# tqfp-sandwich-ui.net
KiCad netlist of a schematic drawn in EAGLE
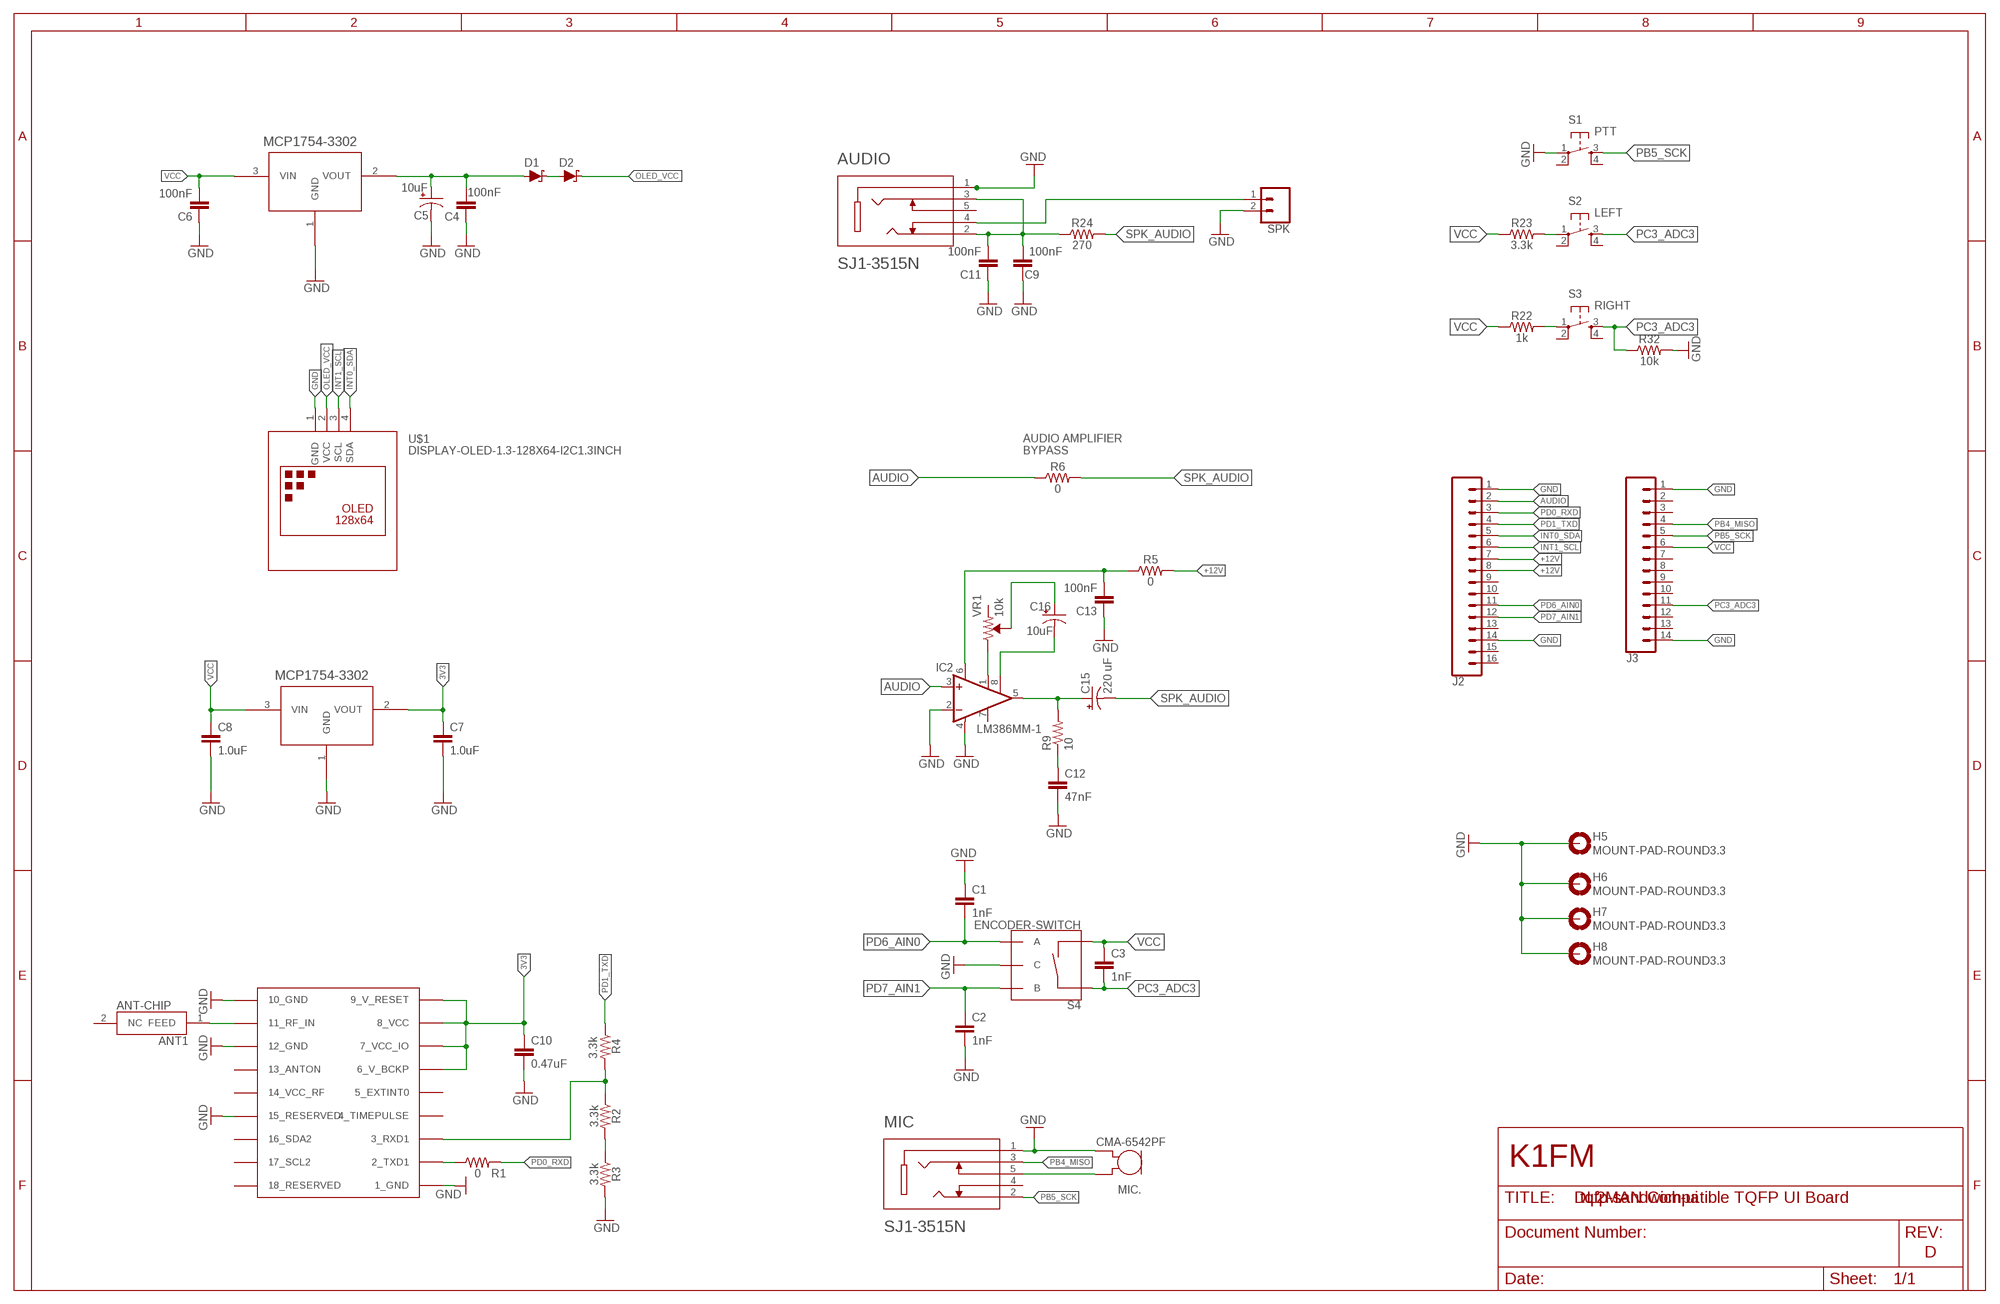
[diagram p0: schematic, sheet 1]

(export (version "E")
  (design (tool "Eeschema 10.0.6"))
  (components
    (comp (ref "ANT-CHIP")
      (value "ANT1")
      (footprint "eagle-import:1575AT43A0040E")
      (fields
        (field (name "MANUFACTURER_PART_NUMBER") "1575AT43A0040E")
        (field (name "MOUSER_PART_NUMBER") "609-1575AT43A0040E")
      )
      (libsource (lib "eagle-import") (part "1575AT43A0040E"))
    )
    (comp (ref "AUDIO")
      (value "SJ1-3515N")
      (footprint "eagle-import:CUI_SJ1-3515N")
      (fields (field (name "MANUFACTURER") "CUI"))
      (libsource (lib "eagle-import") (part "SJ1-3515N"))
    )
    (comp (ref "C1")
      (value "1nF")
      (footprint "eagle-import:0603")
      (libsource (lib "eagle-import") (part "1.0NF/1000PF-0603-50V-10%"))
    )
    (comp (ref "C2")
      (value "1nF")
      (footprint "eagle-import:0603")
      (libsource (lib "eagle-import") (part "1.0NF/1000PF-0603-50V-10%"))
    )
    (comp (ref "C3")
      (value "1nF")
      (footprint "eagle-import:0603")
      (libsource (lib "eagle-import") (part "1.0NF/1000PF-0603-50V-10%"))
    )
    (comp (ref "C4")
      (value "100nF")
      (footprint "eagle-import:0603")
      (libsource (lib "eagle-import") (part "1.0NF/1000PF-0603-50V-10%"))
    )
    (comp (ref "C5")
      (value "10uF")
      (footprint "eagle-import:EIA3216")
      (libsource (lib "eagle-import") (part "10UF-POLAR-EIA3216-16V-10%(TANT)"))
    )
    (comp (ref "C6")
      (value "100nF")
      (footprint "eagle-import:0603")
      (libsource (lib "eagle-import") (part "1.0NF/1000PF-0603-50V-10%"))
    )
    (comp (ref "C7")
      (value "1.0uF")
      (footprint "eagle-import:0603")
      (libsource (lib "eagle-import") (part "1.0UF-0603-16V-10%"))
    )
    (comp (ref "C8")
      (value "1.0uF")
      (footprint "eagle-import:0603")
      (libsource (lib "eagle-import") (part "1.0UF-0603-16V-10%"))
    )
    (comp (ref "C9")
      (value "100nF")
      (footprint "eagle-import:0603")
      (libsource (lib "eagle-import") (part "1.0NF/1000PF-0603-50V-10%"))
    )
    (comp (ref "C10")
      (value "0.47uF")
      (footprint "eagle-import:0603")
      (libsource (lib "eagle-import") (part "0.1UF-0603-25V-5%"))
    )
    (comp (ref "C11")
      (value "100nF")
      (footprint "eagle-import:0603")
      (libsource (lib "eagle-import") (part "1.0NF/1000PF-0603-50V-10%"))
    )
    (comp (ref "C12")
      (value "47nF")
      (footprint "eagle-import:0603")
      (libsource (lib "eagle-import") (part "47NF-0603-25V-5%"))
    )
    (comp (ref "C13")
      (value "100nF")
      (footprint "eagle-import:0603")
      (libsource (lib "eagle-import") (part "1.0NF/1000PF-0603-50V-10%"))
    )
    (comp (ref "C15")
      (value "220 uF")
      (footprint "eagle-import:PANASONIC_C")
      (libsource (lib "eagle-import") (part "CPOL-USC"))
    )
    (comp (ref "C16")
      (value "10uF")
      (footprint "eagle-import:EIA3216")
      (libsource (lib "eagle-import") (part "10UF-POLAR-EIA3216-16V-10%(TANT)"))
    )
    (comp (ref "D1")
      (value "1A/23V/620mV")
      (footprint "eagle-import:SOD-323")
      (libsource (lib "eagle-import") (part "DIODE-SCHOTTKY-BAT20J"))
    )
    (comp (ref "D2")
      (value "1A/23V/620mV")
      (footprint "eagle-import:SOD-323")
      (libsource (lib "eagle-import") (part "DIODE-SCHOTTKY-BAT20J"))
    )
    (comp (ref "GPS1")
      (value "UBLOX_MAX")
      (footprint "eagle-import:UBLOX_MAX")
      (libsource (lib "eagle-import") (part "UBLOX_MAX"))
    )
    (comp (ref "H5")
      (value "MOUNT-PAD-ROUND3.3")
      (footprint "eagle-import:3,3-PAD")
      (libsource (lib "eagle-import") (part "MOUNT-PAD-ROUND3.3"))
    )
    (comp (ref "H6")
      (value "MOUNT-PAD-ROUND3.3")
      (footprint "eagle-import:3,3-PAD")
      (libsource (lib "eagle-import") (part "MOUNT-PAD-ROUND3.3"))
    )
    (comp (ref "H7")
      (value "MOUNT-PAD-ROUND3.3")
      (footprint "eagle-import:3,3-PAD")
      (libsource (lib "eagle-import") (part "MOUNT-PAD-ROUND3.3"))
    )
    (comp (ref "H8")
      (value "MOUNT-PAD-ROUND3.3")
      (footprint "eagle-import:3,3-PAD")
      (libsource (lib "eagle-import") (part "MOUNT-PAD-ROUND3.3"))
    )
    (comp (ref "IC2")
      (value "LM386MM-1")
      (footprint "eagle-import:MMSOP08")
      (libsource (lib "eagle-import") (part "LM386?-MM1"))
    )
    (comp (ref "J2")
      (value "CONN_16")
      (footprint "eagle-import:1X16")
      (libsource (lib "eagle-import") (part "CONN_16"))
    )
    (comp (ref "J3")
      (value "CONN_14")
      (footprint "eagle-import:1X14")
      (libsource (lib "eagle-import") (part "CONN_14"))
    )
    (comp (ref "MIC")
      (value "SJ1-3515N")
      (footprint "eagle-import:CUI_SJ1-3515N")
      (fields (field (name "MANUFACTURER") "CUI"))
      (libsource (lib "eagle-import") (part "SJ1-3515N"))
    )
    (comp (ref "MIC.")
      (value "CMA-6542PF")
      (footprint "eagle-import:CUI_CMA-6542PF")
      (fields (field (name "MANUFACTURER") "CUI INC"))
      (libsource (lib "eagle-import") (part "CMA-6542PF"))
    )
    (comp (ref "R1")
      (value "0")
      (footprint "eagle-import:0603")
      (libsource (lib "eagle-import") (part "3.3KOHM-0603-1/10W-1%"))
    )
    (comp (ref "R2")
      (value "3.3k")
      (footprint "eagle-import:0603")
      (libsource (lib "eagle-import") (part "3.3KOHM-0603-1/10W-1%"))
    )
    (comp (ref "R3")
      (value "3.3k")
      (footprint "eagle-import:0603")
      (libsource (lib "eagle-import") (part "3.3KOHM-0603-1/10W-1%"))
    )
    (comp (ref "R4")
      (value "3.3k")
      (footprint "eagle-import:0603")
      (libsource (lib "eagle-import") (part "3.3KOHM-0603-1/10W-1%"))
    )
    (comp (ref "R5")
      (value "0")
      (footprint "eagle-import:0603")
      (libsource (lib "eagle-import") (part "0OHM-0603-1/10W-5%"))
    )
    (comp (ref "R6")
      (value "0")
      (footprint "eagle-import:0603")
      (libsource (lib "eagle-import") (part "0OHM-0603-1/10W-5%"))
    )
    (comp (ref "R9")
      (value "10")
      (footprint "eagle-import:0603")
      (libsource (lib "eagle-import") (part "10OHM-0603-1/10W-5%"))
    )
    (comp (ref "R22")
      (value "1k")
      (footprint "eagle-import:0603")
      (libsource (lib "eagle-import") (part "1KOHM-0603-1/10W-1%"))
    )
    (comp (ref "R23")
      (value "3.3k")
      (footprint "eagle-import:0603")
      (libsource (lib "eagle-import") (part "3.3KOHM-0603-1/10W-1%"))
    )
    (comp (ref "R24")
      (value "270")
      (footprint "eagle-import:0603")
      (libsource (lib "eagle-import") (part "287OHM-0603-1/10W-1%"))
    )
    (comp (ref "R32")
      (value "10k")
      (footprint "eagle-import:0603")
      (libsource (lib "eagle-import") (part "10KOHM-0603-1/10W-1%"))
    )
    (comp (ref "S1")
      (value "PTT")
      (footprint "eagle-import:DTSM-6")
      (libsource (lib "eagle-import") (part "DTSM-6"))
    )
    (comp (ref "S2")
      (value "LEFT")
      (footprint "eagle-import:DTSM-6")
      (libsource (lib "eagle-import") (part "DTSM-6"))
    )
    (comp (ref "S3")
      (value "RIGHT")
      (footprint "eagle-import:DTSM-6")
      (libsource (lib "eagle-import") (part "DTSM-6"))
    )
    (comp (ref "S4")
      (value "ENCODER-SWITCH")
      (footprint "eagle-import:ROTARY_ENC_PLAIN")
      (libsource (lib "eagle-import") (part "ENCODER-SWITCH"))
    )
    (comp (ref "SPK")
      (value "CONN_02")
      (footprint "eagle-import:1X02")
      (libsource (lib "eagle-import") (part "CONN_02"))
    )
    (comp (ref "U$1")
      (value "DISPLAY-OLED-1.3-128X64-I2C1.3INCH")
      (footprint "eagle-import:DISPLAY-OLED-1.3-128X64-I2C")
      (libsource (lib "eagle-import") (part "DISPLAY-OLED-1.3-128X64-I2C1.3INCH"))
    )
    (comp (ref "U1")
      (value "MCP1754X-XXXXX/C")
      (footprint "eagle-import:SOT-23A_MC")
      (libsource (lib "eagle-import") (part "MCP1754X-XXXXX/C"))
    )
    (comp (ref "U3")
      (value "MCP1754X-XXXXX/C")
      (footprint "eagle-import:SOT-23A_MC")
      (libsource (lib "eagle-import") (part "MCP1754X-XXXXX/C"))
    )
    (comp (ref "VR1")
      (value "10k")
      (footprint "eagle-import:TRIMPOT-SMD-TC33X")
      (libsource (lib "eagle-import") (part "TRIMPOT-SMD-3MM-OPEN-1/10W-25%"))
    )
  )
  (nets
    (net (code "1") (name "+12V") (class "Default")
      (node (ref "J2") (pin "7") (pinfunction "7_7") (pintype "passive"))
      (node (ref "J2") (pin "8") (pinfunction "8_8") (pintype "passive"))
      (node (ref "R5") (pin "2") (pinfunction "2_2") (pintype "passive"))
    )
    (net (code "2") (name "3V3") (class "Default")
      (node (ref "C10") (pin "1") (pinfunction "1_1") (pintype "passive"))
      (node (ref "C7") (pin "1") (pinfunction "1_1") (pintype "passive"))
      (node (ref "GPS1") (pin "6_V_BCKP") (pinfunction "6_V_BCKP_6_V_BCKP") (pintype "bidirectional"))
      (node (ref "GPS1") (pin "7_VCC_IO") (pinfunction "7_VCC_IO_7_VCC_IO") (pintype "power_in"))
      (node (ref "GPS1") (pin "8_VCC") (pinfunction "8_VCC_8_VCC") (pintype "power_in"))
      (node (ref "GPS1") (pin "9_V_RESET") (pinfunction "9_V_RESET_9_V_RESET") (pintype "power_in"))
      (node (ref "U3") (pin "2") (pinfunction "VOUT_2") (pintype "passive"))
    )
    (net (code "3") (name "AUDIO") (class "Default")
      (node (ref "IC2") (pin "3") (pinfunction "+IN_3") (pintype "input"))
      (node (ref "J2") (pin "2") (pinfunction "2_2") (pintype "passive"))
      (node (ref "R6") (pin "1") (pinfunction "1_1") (pintype "passive"))
    )
    (net (code "4") (name "GND") (class "Default")
      (node (ref "AUDIO") (pin "1") (pinfunction "1_1") (pintype "passive"))
      (node (ref "C1") (pin "1") (pinfunction "1_1") (pintype "passive"))
      (node (ref "C10") (pin "2") (pinfunction "2_2") (pintype "passive"))
      (node (ref "C11") (pin "1") (pinfunction "1_1") (pintype "passive"))
      (node (ref "C12") (pin "2") (pinfunction "2_2") (pintype "passive"))
      (node (ref "C13") (pin "1") (pinfunction "1_1") (pintype "passive"))
      (node (ref "C2") (pin "2") (pinfunction "2_2") (pintype "passive"))
      (node (ref "C4") (pin "1") (pinfunction "1_1") (pintype "passive"))
      (node (ref "C5") (pin "-") (pinfunction "-_-") (pintype "passive"))
      (node (ref "C6") (pin "1") (pinfunction "1_1") (pintype "passive"))
      (node (ref "C7") (pin "2") (pinfunction "2_2") (pintype "passive"))
      (node (ref "C8") (pin "2") (pinfunction "2_2") (pintype "passive"))
      (node (ref "C9") (pin "1") (pinfunction "1_1") (pintype "passive"))
      (node (ref "GPS1") (pin "10_GND") (pinfunction "10_GND_10_GND") (pintype "power_in"))
      (node (ref "GPS1") (pin "12_GND") (pinfunction "12_GND_12_GND") (pintype "power_in"))
      (node (ref "GPS1") (pin "15_RESERVED") (pinfunction "15_RESERVED_15_RESERVED") (pintype "bidirectional"))
      (node (ref "GPS1") (pin "1_GND") (pinfunction "1_GND_1_GND") (pintype "power_in"))
      (node (ref "H5") (pin "B3,3") (pinfunction "MOUNT_B3,3") (pintype "passive"))
      (node (ref "H6") (pin "B3,3") (pinfunction "MOUNT_B3,3") (pintype "passive"))
      (node (ref "H7") (pin "B3,3") (pinfunction "MOUNT_B3,3") (pintype "passive"))
      (node (ref "H8") (pin "B3,3") (pinfunction "MOUNT_B3,3") (pintype "passive"))
      (node (ref "IC2") (pin "2") (pinfunction "-IN_2") (pintype "input"))
      (node (ref "IC2") (pin "4") (pinfunction "GND_4") (pintype "power_in"))
      (node (ref "J2") (pin "1") (pinfunction "1_1") (pintype "passive"))
      (node (ref "J2") (pin "14") (pinfunction "14_14") (pintype "passive"))
      (node (ref "J3") (pin "1") (pinfunction "1_1") (pintype "passive"))
      (node (ref "J3") (pin "14") (pinfunction "14_14") (pintype "passive"))
      (node (ref "MIC") (pin "1") (pinfunction "1_1") (pintype "passive"))
      (node (ref "MIC.") (pin "GND") (pinfunction "GND_GND") (pintype "power_in"))
      (node (ref "R3") (pin "2") (pinfunction "2_2") (pintype "passive"))
      (node (ref "R32") (pin "2") (pinfunction "2_2") (pintype "passive"))
      (node (ref "S1") (pin "1") (pinfunction "1_1") (pintype "passive"))
      (node (ref "S4") (pin "C") (pinfunction "C_C") (pintype "bidirectional"))
      (node (ref "SPK") (pin "2") (pinfunction "2_2") (pintype "passive"))
      (node (ref "U$1") (pin "1") (pinfunction "GND_1") (pintype "power_in"))
      (node (ref "U1") (pin "1") (pinfunction "GND_1") (pintype "passive"))
      (node (ref "U3") (pin "1") (pinfunction "GND_1") (pintype "passive"))
    )
    (net (code "5") (name "INT0_SDA") (class "Default")
      (node (ref "J2") (pin "5") (pinfunction "5_5") (pintype "passive"))
      (node (ref "U$1") (pin "4") (pinfunction "SDA_4") (pintype "bidirectional"))
    )
    (net (code "6") (name "INT1_SCL") (class "Default")
      (node (ref "J2") (pin "6") (pinfunction "6_6") (pintype "passive"))
      (node (ref "U$1") (pin "3") (pinfunction "SCL_3") (pintype "bidirectional"))
    )
    (net (code "7") (name "Net-(ANT-CHIP-FEED)") (class "Default")
      (node (ref "ANT-CHIP") (pin "1") (pinfunction "FEED_1") (pintype "input"))
      (node (ref "GPS1") (pin "11_RF_IN") (pinfunction "11_RF_IN_11_RF_IN") (pintype "bidirectional"))
    )
    (net (code "8") (name "Net-(AUDIO-Pad2)") (class "Default")
      (node (ref "AUDIO") (pin "2") (pinfunction "2_2") (pintype "passive"))
      (node (ref "AUDIO") (pin "3") (pinfunction "3_3") (pintype "passive"))
      (node (ref "C11") (pin "2") (pinfunction "2_2") (pintype "passive"))
      (node (ref "C9") (pin "2") (pinfunction "2_2") (pintype "passive"))
      (node (ref "R24") (pin "1") (pinfunction "1_1") (pintype "passive"))
    )
    (net (code "9") (name "Net-(AUDIO-Pad4)") (class "Default")
      (node (ref "AUDIO") (pin "4") (pinfunction "4_4") (pintype "passive"))
      (node (ref "SPK") (pin "1") (pinfunction "1_1") (pintype "passive"))
    )
    (net (code "10") (name "Net-(C12-Pad1)") (class "Default")
      (node (ref "C12") (pin "1") (pinfunction "1_1") (pintype "passive"))
      (node (ref "R9") (pin "1") (pinfunction "1_1") (pintype "passive"))
    )
    (net (code "11") (name "Net-(C16-Pad-)") (class "Default")
      (node (ref "C16") (pin "-") (pinfunction "-_-") (pintype "passive"))
      (node (ref "IC2") (pin "8") (pinfunction "GAIN_8") (pintype "passive"))
    )
    (net (code "12") (name "Net-(D1-PadC)") (class "Default")
      (node (ref "D1") (pin "C") (pinfunction "C_C") (pintype "passive"))
      (node (ref "D2") (pin "A") (pinfunction "A_A") (pintype "passive"))
    )
    (net (code "13") (name "Net-(GPS1-Pad2_TXD1)") (class "Default")
      (node (ref "GPS1") (pin "2_TXD1") (pinfunction "2_TXD1_2_TXD1") (pintype "bidirectional"))
      (node (ref "R1") (pin "1") (pinfunction "1_1") (pintype "passive"))
    )
    (net (code "14") (name "Net-(GPS1-Pad3_RXD1)") (class "Default")
      (node (ref "GPS1") (pin "3_RXD1") (pinfunction "3_RXD1_3_RXD1") (pintype "bidirectional"))
      (node (ref "R2") (pin "1") (pinfunction "1_1") (pintype "passive"))
      (node (ref "R4") (pin "2") (pinfunction "2_2") (pintype "passive"))
    )
    (net (code "15") (name "Net-(IC2-OUT)") (class "Default")
      (node (ref "C15") (pin "+") (pinfunction "+_+") (pintype "passive"))
      (node (ref "IC2") (pin "5") (pinfunction "OUT_5") (pintype "output"))
      (node (ref "R9") (pin "2") (pinfunction "2_2") (pintype "passive"))
    )
    (net (code "16") (name "Net-(IC2-VS)") (class "Default")
      (node (ref "C13") (pin "2") (pinfunction "2_2") (pintype "passive"))
      (node (ref "IC2") (pin "6") (pinfunction "VS_6") (pintype "power_in"))
      (node (ref "R5") (pin "1") (pinfunction "1_1") (pintype "passive"))
    )
    (net (code "17") (name "Net-(MIC-Pad5)") (class "Default")
      (node (ref "MIC") (pin "5") (pinfunction "5_5") (pintype "passive"))
      (node (ref "MIC.") (pin "OUT") (pinfunction "OUT_OUT") (pintype "output"))
    )
    (net (code "18") (name "Net-(R2-Pad2)") (class "Default")
      (node (ref "R2") (pin "2") (pinfunction "2_2") (pintype "passive"))
      (node (ref "R3") (pin "1") (pinfunction "1_1") (pintype "passive"))
    )
    (net (code "19") (name "Net-(R22-Pad2)") (class "Default")
      (node (ref "R22") (pin "2") (pinfunction "2_2") (pintype "passive"))
      (node (ref "S3") (pin "1") (pinfunction "1_1") (pintype "passive"))
    )
    (net (code "20") (name "Net-(R23-Pad2)") (class "Default")
      (node (ref "R23") (pin "2") (pinfunction "2_2") (pintype "passive"))
      (node (ref "S2") (pin "1") (pinfunction "1_1") (pintype "passive"))
    )
    (net (code "21") (name "Net-(U1-VOUT)") (class "Default")
      (node (ref "C4") (pin "2") (pinfunction "2_2") (pintype "passive"))
      (node (ref "C5") (pin "+") (pinfunction "+_+") (pintype "passive"))
      (node (ref "D1") (pin "A") (pinfunction "A_A") (pintype "passive"))
      (node (ref "U1") (pin "2") (pinfunction "VOUT_2") (pintype "passive"))
    )
    (net (code "22") (name "Net-(VR1-CW)") (class "Default")
      (node (ref "IC2") (pin "1") (pinfunction "GAIN_1") (pintype "passive"))
      (node (ref "VR1") (pin "1") (pinfunction "CW_1") (pintype "passive"))
    )
    (net (code "23") (name "Net-(VR1-WIPER)") (class "Default")
      (node (ref "C16") (pin "+") (pinfunction "+_+") (pintype "passive"))
      (node (ref "VR1") (pin "2") (pinfunction "WIPER_2") (pintype "passive"))
    )
    (net (code "24") (name "OLED_VCC") (class "Default")
      (node (ref "D2") (pin "C") (pinfunction "C_C") (pintype "passive"))
      (node (ref "U$1") (pin "2") (pinfunction "VCC_2") (pintype "power_in"))
    )
    (net (code "25") (name "PB4_MISO") (class "Default")
      (node (ref "J3") (pin "4") (pinfunction "4_4") (pintype "passive"))
      (node (ref "MIC") (pin "3") (pinfunction "3_3") (pintype "passive"))
    )
    (net (code "26") (name "PB5_SCK") (class "Default")
      (node (ref "J3") (pin "5") (pinfunction "5_5") (pintype "passive"))
      (node (ref "MIC") (pin "2") (pinfunction "2_2") (pintype "passive"))
      (node (ref "S1") (pin "3") (pinfunction "3_3") (pintype "passive"))
    )
    (net (code "27") (name "PC3_ADC3") (class "Default")
      (node (ref "C3") (pin "2") (pinfunction "2_2") (pintype "passive"))
      (node (ref "J3") (pin "11") (pinfunction "11_11") (pintype "passive"))
      (node (ref "R32") (pin "1") (pinfunction "1_1") (pintype "passive"))
      (node (ref "S2") (pin "3") (pinfunction "3_3") (pintype "passive"))
      (node (ref "S3") (pin "3") (pinfunction "3_3") (pintype "passive"))
      (node (ref "S4") (pin "SW+") (pinfunction "SW+_SW+") (pintype "bidirectional"))
    )
    (net (code "28") (name "PD0_RXD") (class "Default")
      (node (ref "J2") (pin "3") (pinfunction "3_3") (pintype "passive"))
      (node (ref "R1") (pin "2") (pinfunction "2_2") (pintype "passive"))
    )
    (net (code "29") (name "PD1_TXD") (class "Default")
      (node (ref "J2") (pin "4") (pinfunction "4_4") (pintype "passive"))
      (node (ref "R4") (pin "1") (pinfunction "1_1") (pintype "passive"))
    )
    (net (code "30") (name "PD6_AIN0") (class "Default")
      (node (ref "C1") (pin "2") (pinfunction "2_2") (pintype "passive"))
      (node (ref "J2") (pin "11") (pinfunction "11_11") (pintype "passive"))
      (node (ref "S4") (pin "A") (pinfunction "A_A") (pintype "bidirectional"))
    )
    (net (code "31") (name "PD7_AIN1") (class "Default")
      (node (ref "C2") (pin "1") (pinfunction "1_1") (pintype "passive"))
      (node (ref "J2") (pin "12") (pinfunction "12_12") (pintype "passive"))
      (node (ref "S4") (pin "B") (pinfunction "B_B") (pintype "bidirectional"))
    )
    (net (code "32") (name "SPK_AUDIO") (class "Default")
      (node (ref "C15") (pin "-") (pinfunction "-_-") (pintype "passive"))
      (node (ref "R24") (pin "2") (pinfunction "2_2") (pintype "passive"))
      (node (ref "R6") (pin "2") (pinfunction "2_2") (pintype "passive"))
    )
    (net (code "33") (name "VCC") (class "Default")
      (node (ref "C3") (pin "1") (pinfunction "1_1") (pintype "passive"))
      (node (ref "C6") (pin "2") (pinfunction "2_2") (pintype "passive"))
      (node (ref "C8") (pin "1") (pinfunction "1_1") (pintype "passive"))
      (node (ref "J3") (pin "6") (pinfunction "6_6") (pintype "passive"))
      (node (ref "R22") (pin "1") (pinfunction "1_1") (pintype "passive"))
      (node (ref "R23") (pin "1") (pinfunction "1_1") (pintype "passive"))
      (node (ref "S4") (pin "SW-") (pinfunction "SW-_SW-") (pintype "bidirectional"))
      (node (ref "U1") (pin "3") (pinfunction "VIN_3") (pintype "passive"))
      (node (ref "U3") (pin "3") (pinfunction "VIN_3") (pintype "passive"))
    )
    (net (code "34") (name "unconnected-(ANT-CHIP-NC-Pad2)") (class "Default")
      (node (ref "ANT-CHIP") (pin "2") (pinfunction "NC_2") (pintype "no_connect"))
    )
    (net (code "35") (name "unconnected-(AUDIO-Pad5)") (class "Default")
      (node (ref "AUDIO") (pin "5") (pinfunction "5_5") (pintype "passive"))
    )
    (net (code "36") (name "unconnected-(GPS1-Pad4_TIMEPULSE)") (class "Default")
      (node (ref "GPS1") (pin "4_TIMEPULSE") (pinfunction "4_TIMEPULSE_4_TIMEPULSE") (pintype "bidirectional"))
    )
    (net (code "37") (name "unconnected-(GPS1-Pad5_EXTINT0)") (class "Default")
      (node (ref "GPS1") (pin "5_EXTINT0") (pinfunction "5_EXTINT0_5_EXTINT0") (pintype "bidirectional"))
    )
    (net (code "38") (name "unconnected-(GPS1-Pad13_ANTON)") (class "Default")
      (node (ref "GPS1") (pin "13_ANTON") (pinfunction "13_ANTON_13_ANTON") (pintype "bidirectional"))
    )
    (net (code "39") (name "unconnected-(GPS1-Pad14_VCC_RF)") (class "Default")
      (node (ref "GPS1") (pin "14_VCC_RF") (pinfunction "14_VCC_RF_14_VCC_RF") (pintype "bidirectional"))
    )
    (net (code "40") (name "unconnected-(GPS1-Pad16_SDA2)") (class "Default")
      (node (ref "GPS1") (pin "16_SDA2") (pinfunction "16_SDA2_16_SDA2") (pintype "bidirectional"))
    )
    (net (code "41") (name "unconnected-(GPS1-Pad17_SCL2)") (class "Default")
      (node (ref "GPS1") (pin "17_SCL2") (pinfunction "17_SCL2_17_SCL2") (pintype "bidirectional"))
    )
    (net (code "42") (name "unconnected-(GPS1-Pad18_RESERVED)") (class "Default")
      (node (ref "GPS1") (pin "18_RESERVED") (pinfunction "18_RESERVED_18_RESERVED") (pintype "bidirectional"))
    )
    (net (code "43") (name "unconnected-(IC2-BYPASS-Pad7)") (class "Default")
      (node (ref "IC2") (pin "7") (pinfunction "BYPASS_7") (pintype "passive"))
    )
    (net (code "44") (name "unconnected-(J2-Pad9)") (class "Default")
      (node (ref "J2") (pin "9") (pinfunction "9_9") (pintype "passive"))
    )
    (net (code "45") (name "unconnected-(J2-Pad10)") (class "Default")
      (node (ref "J2") (pin "10") (pinfunction "10_10") (pintype "passive"))
    )
    (net (code "46") (name "unconnected-(J2-Pad13)") (class "Default")
      (node (ref "J2") (pin "13") (pinfunction "13_13") (pintype "passive"))
    )
    (net (code "47") (name "unconnected-(J2-Pad15)") (class "Default")
      (node (ref "J2") (pin "15") (pinfunction "15_15") (pintype "passive"))
    )
    (net (code "48") (name "unconnected-(J2-Pad16)") (class "Default")
      (node (ref "J2") (pin "16") (pinfunction "16_16") (pintype "passive"))
    )
    (net (code "49") (name "unconnected-(J3-Pad2)") (class "Default")
      (node (ref "J3") (pin "2") (pinfunction "2_2") (pintype "passive"))
    )
    (net (code "50") (name "unconnected-(J3-Pad3)") (class "Default")
      (node (ref "J3") (pin "3") (pinfunction "3_3") (pintype "passive"))
    )
    (net (code "51") (name "unconnected-(J3-Pad7)") (class "Default")
      (node (ref "J3") (pin "7") (pinfunction "7_7") (pintype "passive"))
    )
    (net (code "52") (name "unconnected-(J3-Pad8)") (class "Default")
      (node (ref "J3") (pin "8") (pinfunction "8_8") (pintype "passive"))
    )
    (net (code "53") (name "unconnected-(J3-Pad9)") (class "Default")
      (node (ref "J3") (pin "9") (pinfunction "9_9") (pintype "passive"))
    )
    (net (code "54") (name "unconnected-(J3-Pad10)") (class "Default")
      (node (ref "J3") (pin "10") (pinfunction "10_10") (pintype "passive"))
    )
    (net (code "55") (name "unconnected-(J3-Pad12)") (class "Default")
      (node (ref "J3") (pin "12") (pinfunction "12_12") (pintype "passive"))
    )
    (net (code "56") (name "unconnected-(J3-Pad13)") (class "Default")
      (node (ref "J3") (pin "13") (pinfunction "13_13") (pintype "passive"))
    )
    (net (code "57") (name "unconnected-(MIC-Pad4)") (class "Default")
      (node (ref "MIC") (pin "4") (pinfunction "4_4") (pintype "passive"))
    )
    (net (code "58") (name "unconnected-(S1-Pad2)") (class "Default")
      (node (ref "S1") (pin "2") (pinfunction "2_2") (pintype "passive"))
    )
    (net (code "59") (name "unconnected-(S1-Pad4)") (class "Default")
      (node (ref "S1") (pin "4") (pinfunction "4_4") (pintype "passive"))
    )
    (net (code "60") (name "unconnected-(S2-Pad2)") (class "Default")
      (node (ref "S2") (pin "2") (pinfunction "2_2") (pintype "passive"))
    )
    (net (code "61") (name "unconnected-(S2-Pad4)") (class "Default")
      (node (ref "S2") (pin "4") (pinfunction "4_4") (pintype "passive"))
    )
    (net (code "62") (name "unconnected-(S3-Pad2)") (class "Default")
      (node (ref "S3") (pin "2") (pinfunction "2_2") (pintype "passive"))
    )
    (net (code "63") (name "unconnected-(S3-Pad4)") (class "Default")
      (node (ref "S3") (pin "4") (pinfunction "4_4") (pintype "passive"))
    )
    (net (code "64") (name "unconnected-(VR1-CCW-Pad3)") (class "Default")
      (node (ref "VR1") (pin "3") (pinfunction "CCW_3") (pintype "passive"))
    )
  )
)
